# gps_board.net
KiCad netlist of a schematic drawn in EAGLE
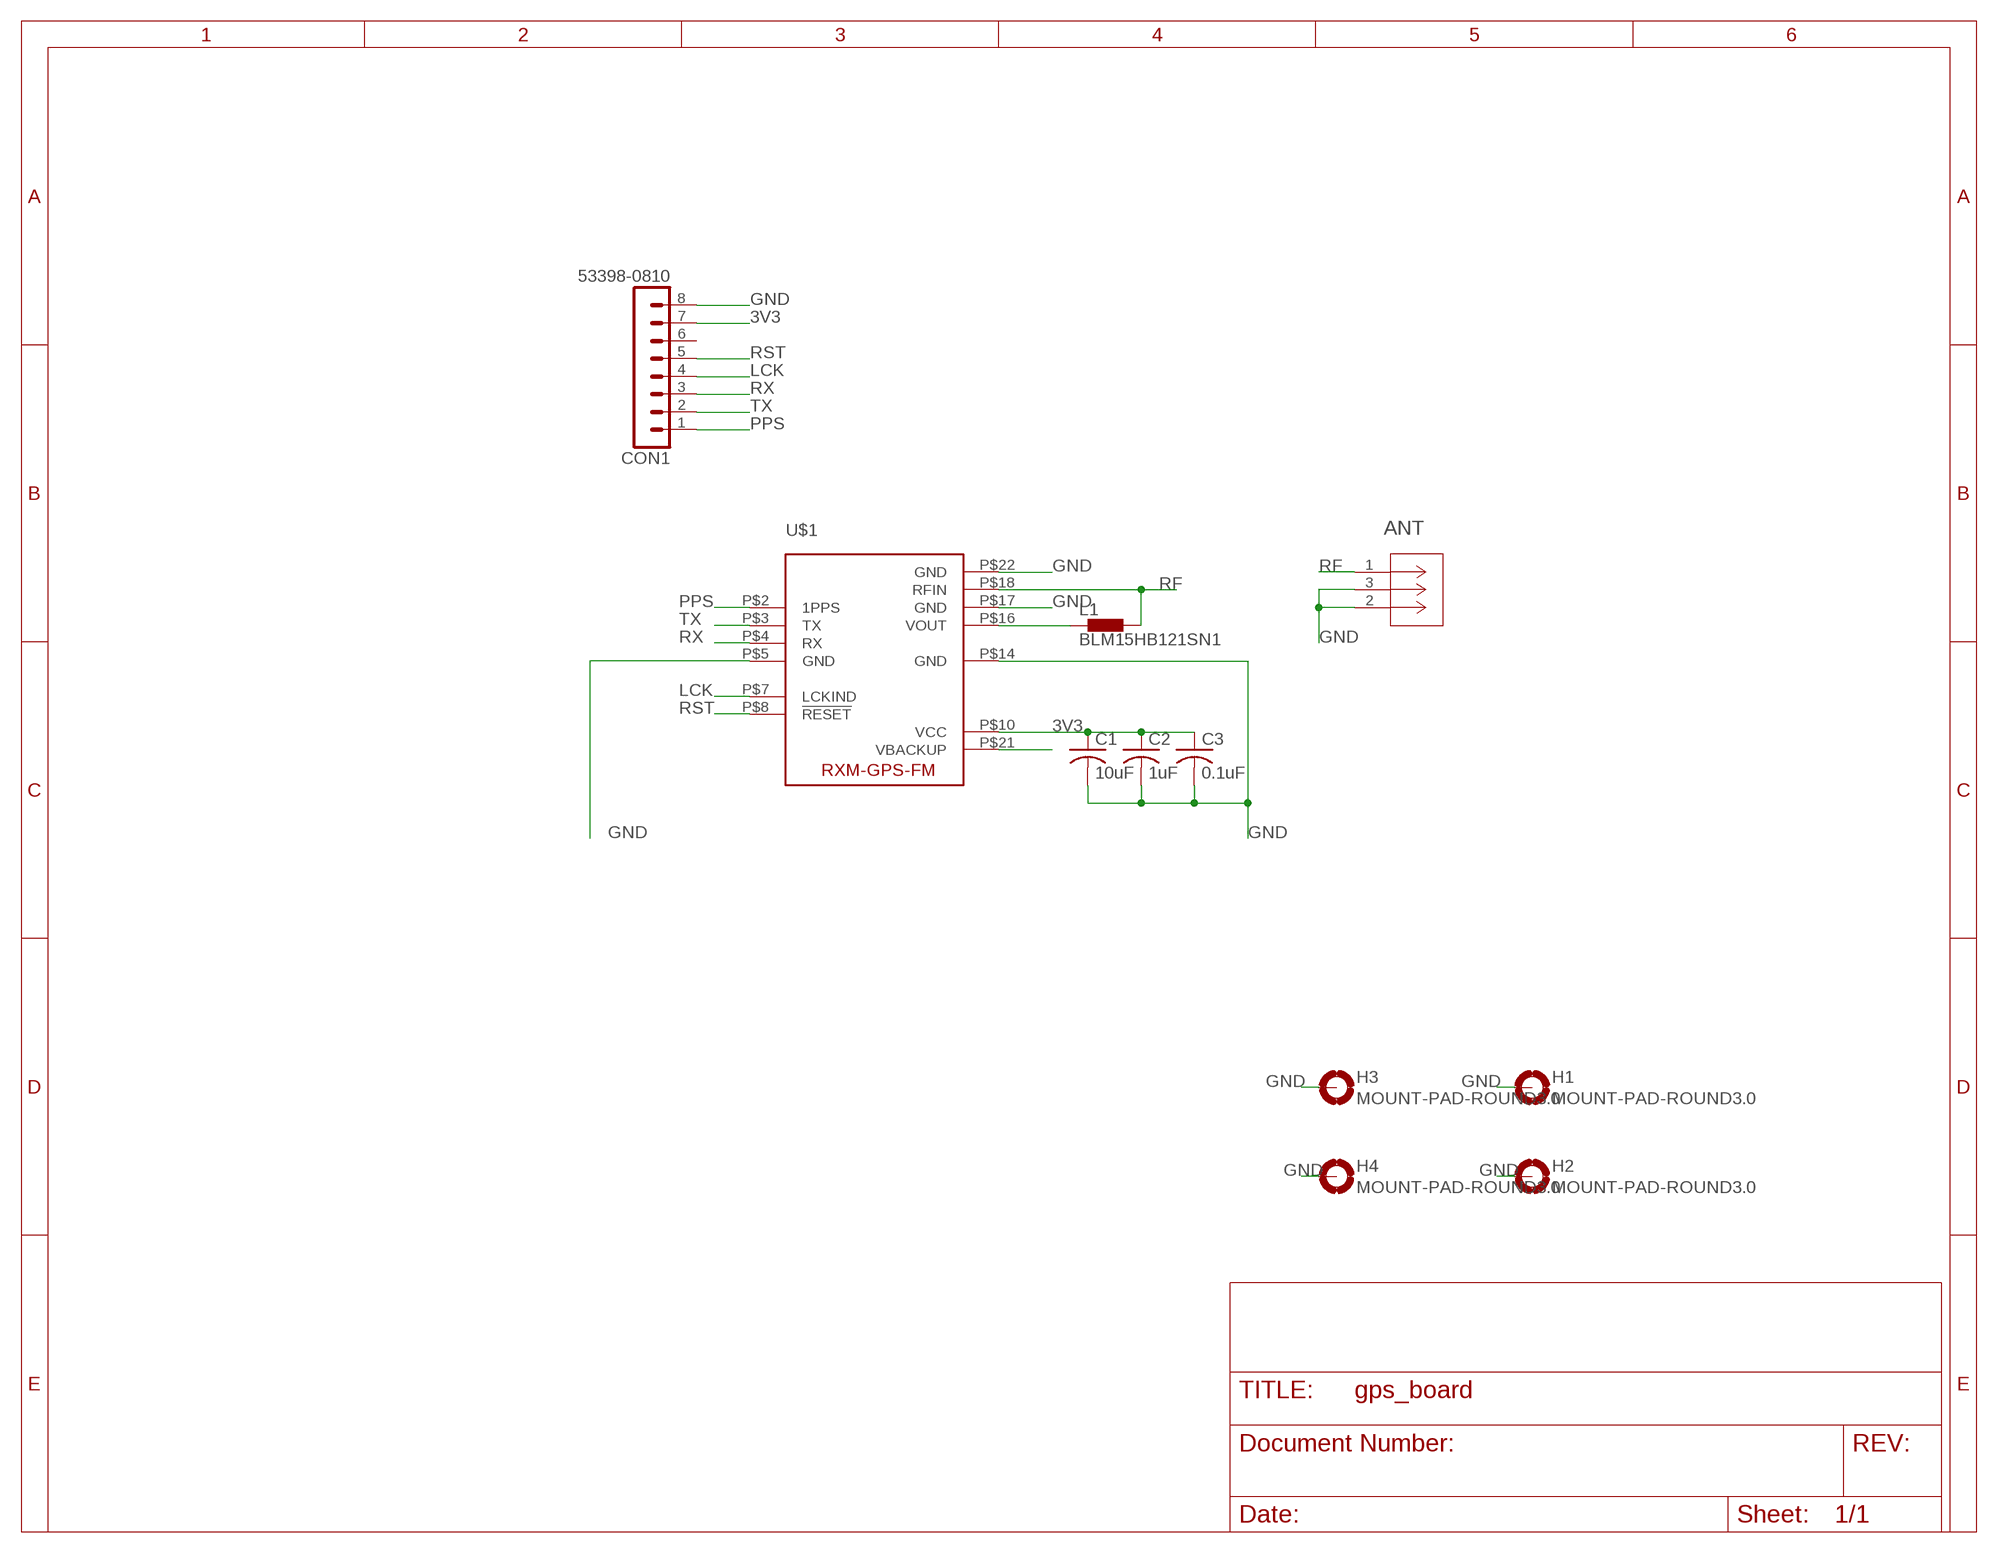
[diagram p0: schematic, sheet 1]

(export (version "E")
  (design (tool "Eeschema 10.0.6"))
  (components
    (comp (ref "ANT")
      (value "U.FL-R-SMT-1(10)")
      (footprint "eagle-import:CONN_R-SMT-1(10)")
      (fields (field (name "COPYRIGHT") "Copyright (C) 2018 Accelerated Designs. All rights reserved"))
      (libsource (lib "eagle-import") (part "U.FL-R-SMT-1(10)"))
    )
    (comp (ref "C1")
      (value "10uF")
      (footprint "eagle-import:C0603")
      (libsource (lib "eagle-import") (part "C-USC0603"))
    )
    (comp (ref "C2")
      (value "1uF")
      (footprint "eagle-import:C0603")
      (libsource (lib "eagle-import") (part "C-USC0603"))
    )
    (comp (ref "C3")
      (value "0.1uF")
      (footprint "eagle-import:C0603")
      (libsource (lib "eagle-import") (part "C-USC0603"))
    )
    (comp (ref "CON1")
      (value "53398-0810")
      (footprint "eagle-import:53398-0810")
      (libsource (lib "eagle-import") (part "53398-0810"))
    )
    (comp (ref "H1")
      (value "MOUNT-PAD-ROUND3.0")
      (footprint "eagle-import:3,0-PAD")
      (libsource (lib "eagle-import") (part "MOUNT-PAD-ROUND3.0"))
    )
    (comp (ref "H2")
      (value "MOUNT-PAD-ROUND3.0")
      (footprint "eagle-import:3,0-PAD")
      (libsource (lib "eagle-import") (part "MOUNT-PAD-ROUND3.0"))
    )
    (comp (ref "H3")
      (value "MOUNT-PAD-ROUND3.0")
      (footprint "eagle-import:3,0-PAD")
      (libsource (lib "eagle-import") (part "MOUNT-PAD-ROUND3.0"))
    )
    (comp (ref "H4")
      (value "MOUNT-PAD-ROUND3.0")
      (footprint "eagle-import:3,0-PAD")
      (libsource (lib "eagle-import") (part "MOUNT-PAD-ROUND3.0"))
    )
    (comp (ref "L1")
      (value "BLM15HB121SN1")
      (footprint "eagle-import:0402")
      (libsource (lib "eagle-import") (part "BLM15HB121SN1"))
    )
    (comp (ref "U$1")
      (value "RXM-GPS-FM")
      (footprint "eagle-import:RXM-GPS-FM")
      (libsource (lib "eagle-import") (part "RXM-GPS-FM"))
    )
  )
  (nets
    (net (code "1") (name "/3V3") (class "Default")
      (node (ref "C1") (pin "1") (pinfunction "1_1") (pintype "passive"))
      (node (ref "C2") (pin "1") (pinfunction "1_1") (pintype "passive"))
      (node (ref "C3") (pin "1") (pinfunction "1_1") (pintype "passive"))
      (node (ref "CON1") (pin "7") (pinfunction "7_7") (pintype "passive"))
      (node (ref "U$1") (pin "P$10") (pinfunction "VCC_P$10") (pintype "bidirectional"))
    )
    (net (code "2") (name "/GND") (class "Default")
      (node (ref "ANT") (pin "2") (pinfunction "2_2") (pintype "passive"))
      (node (ref "ANT") (pin "3") (pinfunction "3_3") (pintype "passive"))
      (node (ref "C1") (pin "2") (pinfunction "2_2") (pintype "passive"))
      (node (ref "C2") (pin "2") (pinfunction "2_2") (pintype "passive"))
      (node (ref "C3") (pin "2") (pinfunction "2_2") (pintype "passive"))
      (node (ref "CON1") (pin "8") (pinfunction "8_8") (pintype "passive"))
      (node (ref "H1") (pin "B3,0") (pinfunction "MOUNT_B3,0") (pintype "passive"))
      (node (ref "H2") (pin "B3,0") (pinfunction "MOUNT_B3,0") (pintype "passive"))
      (node (ref "H3") (pin "B3,0") (pinfunction "MOUNT_B3,0") (pintype "passive"))
      (node (ref "H4") (pin "B3,0") (pinfunction "MOUNT_B3,0") (pintype "passive"))
      (node (ref "U$1") (pin "P$14") (pinfunction "GND_P$14") (pintype "bidirectional"))
      (node (ref "U$1") (pin "P$17") (pinfunction "GND_P$17") (pintype "bidirectional"))
      (node (ref "U$1") (pin "P$22") (pinfunction "GND_P$22") (pintype "bidirectional"))
      (node (ref "U$1") (pin "P$5") (pinfunction "GND_P$5") (pintype "bidirectional"))
    )
    (net (code "3") (name "/LCK") (class "Default")
      (node (ref "CON1") (pin "4") (pinfunction "4_4") (pintype "passive"))
      (node (ref "U$1") (pin "P$7") (pinfunction "LCKIND_P$7") (pintype "bidirectional"))
    )
    (net (code "4") (name "/PPS") (class "Default")
      (node (ref "CON1") (pin "1") (pinfunction "1_1") (pintype "passive"))
      (node (ref "U$1") (pin "P$2") (pinfunction "1PPS_P$2") (pintype "bidirectional"))
    )
    (net (code "5") (name "/RF") (class "Default")
      (node (ref "ANT") (pin "1") (pinfunction "1_1") (pintype "passive"))
      (node (ref "L1") (pin "2") (pinfunction "2_2") (pintype "passive"))
      (node (ref "U$1") (pin "P$18") (pinfunction "RFIN_P$18") (pintype "bidirectional"))
    )
    (net (code "6") (name "/RST") (class "Default")
      (node (ref "CON1") (pin "5") (pinfunction "5_5") (pintype "passive"))
      (node (ref "U$1") (pin "P$8") (pinfunction "~{RESET}_P$8") (pintype "bidirectional"))
    )
    (net (code "7") (name "/RX") (class "Default")
      (node (ref "CON1") (pin "3") (pinfunction "3_3") (pintype "passive"))
      (node (ref "U$1") (pin "P$4") (pinfunction "RX_P$4") (pintype "bidirectional"))
    )
    (net (code "8") (name "/TX") (class "Default")
      (node (ref "CON1") (pin "2") (pinfunction "2_2") (pintype "passive"))
      (node (ref "U$1") (pin "P$3") (pinfunction "TX_P$3") (pintype "bidirectional"))
    )
    (net (code "9") (name "Net-(U$1-VOUT)") (class "Default")
      (node (ref "L1") (pin "1") (pinfunction "1_1") (pintype "passive"))
      (node (ref "U$1") (pin "P$16") (pinfunction "VOUT_P$16") (pintype "bidirectional"))
    )
    (net (code "10") (name "unconnected-(CON1-Pad6)") (class "Default")
      (node (ref "CON1") (pin "6") (pinfunction "6_6") (pintype "passive"))
    )
    (net (code "11") (name "unconnected-(U$1-VBACKUP-PadP$21)") (class "Default")
      (node (ref "U$1") (pin "P$21") (pinfunction "VBACKUP_P$21") (pintype "bidirectional"))
    )
  )
)
